# Escorna_CPU_2_40Amt.net
KiCad netlist of a schematic drawn in EAGLE
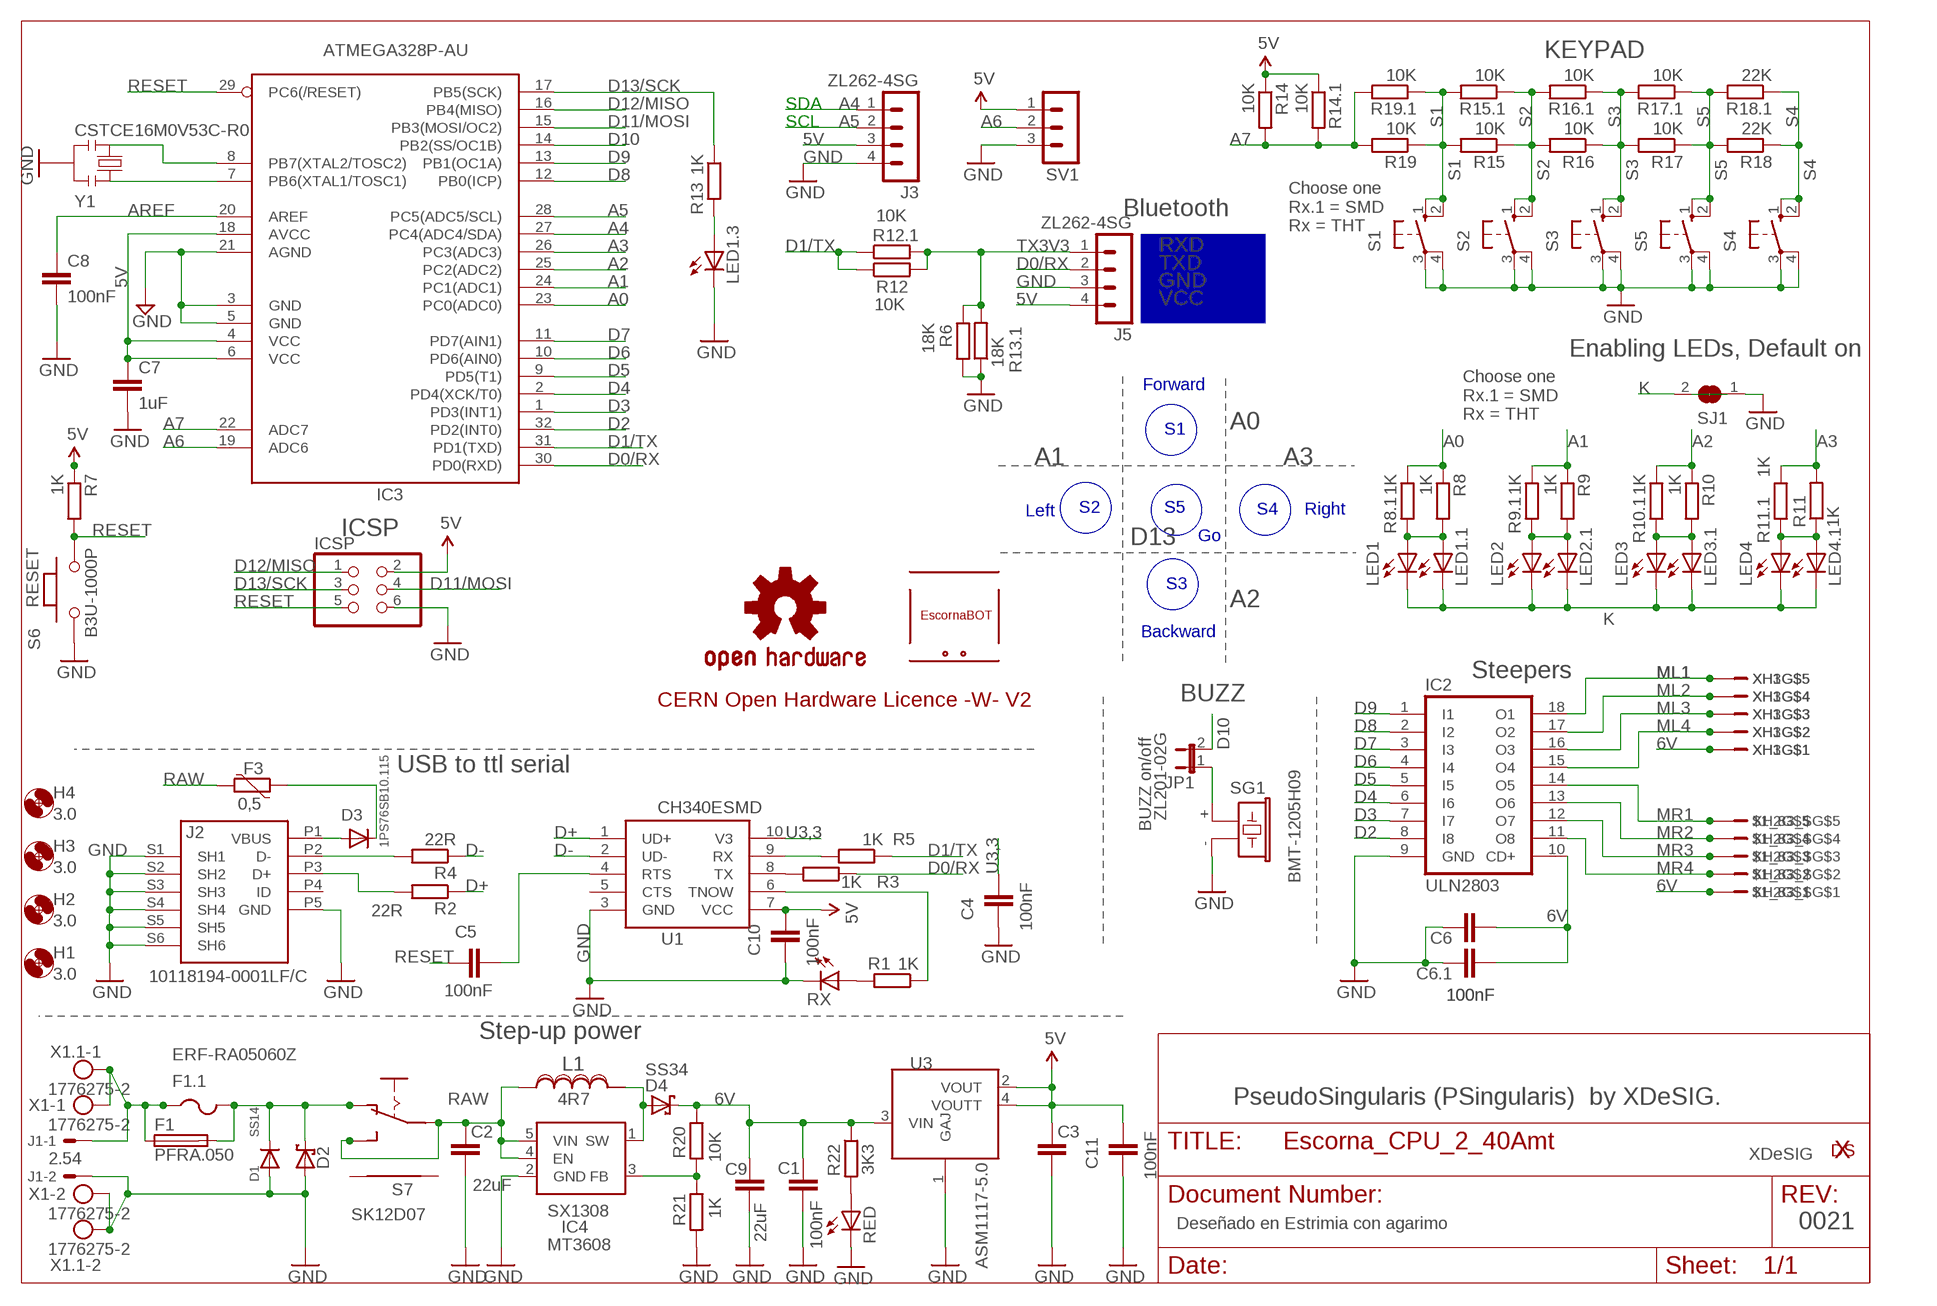
[diagram p0: schematic, sheet 1]

(export (version "E")
  (design (tool "Eeschema 10.0.6"))
  (components
    (comp (ref "$1_82_$")
      (value "XDESIG_XDESIG21")
      (footprint "eagle-import:XDESIG_XDESIG")
      (libsource (lib "eagle-import") (part "XDESIG_XDESIG21"))
    )
    (comp (ref "$1_83_$")
      (value "B5B-XH-A")
      (footprint "eagle-import:B5B-XH-A")
      (libsource (lib "eagle-import") (part "B5B-XH-A"))
    )
    (comp (ref "C1")
      (value "100nF")
      (footprint "eagle-import:C0603-ROUND")
      (fields (field (name "PART_NUMBER") "cl10b104kbnc"))
      (libsource (lib "eagle-import") (part "0015_100NF_0603"))
    )
    (comp (ref "C2")
      (value "22uF")
      (footprint "eagle-import:C1206K")
      (libsource (lib "eagle-import") (part "C-EUC1206K"))
    )
    (comp (ref "C3")
      (value "10uF")
      (footprint "eagle-import:C1206K")
      (libsource (lib "eagle-import") (part "C-EUC1206K"))
    )
    (comp (ref "C4")
      (value "100nF")
      (footprint "eagle-import:C0603-ROUND")
      (fields (field (name "PART_NUMBER") "cl10b104kbnc"))
      (libsource (lib "eagle-import") (part "0015_100NF_0603"))
    )
    (comp (ref "C5")
      (value "100nF")
      (footprint "eagle-import:C0603-ROUND")
      (fields (field (name "PART_NUMBER") "cl10b104kbnc"))
      (libsource (lib "eagle-import") (part "0015_100NF_0603"))
    )
    (comp (ref "C6")
      (value "100nF")
      (footprint "eagle-import:C025-024X044")
      (libsource (lib "eagle-import") (part "C-EU025-024X044"))
    )
    (comp (ref "C6.1")
      (value "100nF")
      (footprint "eagle-import:C0603K")
      (libsource (lib "eagle-import") (part "C-EUC0603K"))
    )
    (comp (ref "C7")
      (value "1uF")
      (footprint "eagle-import:C0603-ROUND")
      (fields (field (name "PART_NUMBER") "1uF_0603/GRM188R61E105KA12D"))
      (libsource (lib "eagle-import") (part "0006_1UF_0603/GRM188R61E105KA12D"))
    )
    (comp (ref "C8")
      (value "100nF")
      (footprint "eagle-import:C0603-ROUND")
      (fields (field (name "PART_NUMBER") "cl10b104kbnc"))
      (libsource (lib "eagle-import") (part "0015_100NF_0603"))
    )
    (comp (ref "C9")
      (value "22uF")
      (footprint "eagle-import:C1206K")
      (libsource (lib "eagle-import") (part "C-EUC1206K"))
    )
    (comp (ref "C10")
      (value "100nF")
      (footprint "eagle-import:C0603-ROUND")
      (fields (field (name "PART_NUMBER") "cl10b104kbnc"))
      (libsource (lib "eagle-import") (part "0015_100NF_0603"))
    )
    (comp (ref "C11")
      (value "100nF")
      (footprint "eagle-import:C0603-ROUND")
      (fields (field (name "PART_NUMBER") "cl10b104kbnc"))
      (libsource (lib "eagle-import") (part "0015_100NF_0603"))
    )
    (comp (ref "D1")
      (value "SS14")
      (footprint "eagle-import:SMADIODE")
      (libsource (lib "eagle-import") (part "DIODESMA"))
    )
    (comp (ref "D2")
      (value "1N5817")
      (footprint "eagle-import:DO41-10")
      (libsource (lib "eagle-import") (part "P4KEXX"))
    )
    (comp (ref "D3")
      (value "1PS76SB10.115")
      (footprint "eagle-import:SOD-323F")
      (libsource (lib "eagle-import") (part "DIODESOD-323F"))
    )
    (comp (ref "D4")
      (value "SS34")
      (footprint "eagle-import:DIODE_SMA")
      (libsource (lib "eagle-import") (part "DIODE_SCHOTTKY-DIODESMA"))
    )
    (comp (ref "ESC")
      (value "ESCORNABOT")
      (footprint "eagle-import:ESCORNA_PEQUE")
      (libsource (lib "eagle-import") (part "ESCORNABOT"))
    )
    (comp (ref "F1")
      (value "PFRA.050")
      (footprint "eagle-import:TE5")
      (libsource (lib "eagle-import") (part "FUSETE5"))
    )
    (comp (ref "F1.1")
      (value "ERF-RA05060Z")
      (footprint "eagle-import:R1206")
      (libsource (lib "eagle-import") (part "PTCFUSE-1206"))
    )
    (comp (ref "F3")
      (value "0,5")
      (footprint "eagle-import:R1206")
      (libsource (lib "eagle-import") (part "PTC1206L"))
    )
    (comp (ref "H1")
      (value "3.0")
      (footprint "eagle-import:3,0")
      (libsource (lib "eagle-import") (part "MOUNT-HOLE3.0"))
    )
    (comp (ref "H2")
      (value "3.0")
      (footprint "eagle-import:3,0")
      (libsource (lib "eagle-import") (part "MOUNT-HOLE3.0"))
    )
    (comp (ref "H3")
      (value "3.0")
      (footprint "eagle-import:3,0")
      (libsource (lib "eagle-import") (part "MOUNT-HOLE3.0"))
    )
    (comp (ref "H4")
      (value "3.0")
      (footprint "eagle-import:3,0")
      (libsource (lib "eagle-import") (part "MOUNT-HOLE3.0"))
    )
    (comp (ref "IC2")
      (value "ULN2803")
      (footprint "eagle-import:DIL18")
      (libsource (lib "eagle-import") (part "ULN2803A"))
    )
    (comp (ref "IC3")
      (value "ATMEGA328P-AU")
      (footprint "eagle-import:TQFP32-08")
      (libsource (lib "eagle-import") (part "0265_ATMEGA328P-AU"))
    )
    (comp (ref "IC4")
      (value "SX1308")
      (footprint "eagle-import:SOT23-6")
      (libsource (lib "eagle-import") (part "SX1308"))
    )
    (comp (ref "ICSP")
      (value "0114_PH254-203DF118A00V")
      (footprint "eagle-import:2X03")
      (fields (field (name "PART_NUMBER") "PH254-203DF118A00V"))
      (libsource (lib "eagle-import") (part "0114_PH254-203DF118A00V"))
    )
    (comp (ref "J1")
      (value "2.54")
      (footprint "eagle-import:6410-02")
      (libsource (lib "eagle-import") (part "22-?-0227-2021"))
    )
    (comp (ref "J2")
      (value "10118194-0001LF/C")
      (footprint "eagle-import:SMARTPRJ_CON2_USB_MICRO_B_AT")
      (libsource (lib "eagle-import") (part "SMARTPRJ_MYCON2_USB-MINI-B"))
    )
    (comp (ref "J3")
      (value "ZL262-4SG")
      (footprint "eagle-import:MA04-1")
      (libsource (lib "eagle-import") (part "MA04-1"))
    )
    (comp (ref "J5")
      (value "ZL262-4SG")
      (footprint "eagle-import:MA04-1")
      (libsource (lib "eagle-import") (part "MA04-1"))
    )
    (comp (ref "JP1")
      (value "ZL201-02G")
      (footprint "eagle-import:JP1")
      (libsource (lib "eagle-import") (part "JP1E"))
    )
    (comp (ref "L1")
      (value "4R7")
      (footprint "eagle-import:SRN6045")
      (fields (field (name "MF") "Bourns") (field (name "MP") "SRN6045-330M"))
      (libsource (lib "eagle-import") (part "SRN6045-330M6045"))
    )
    (comp (ref "LED1")
      (value "LED3MM")
      (footprint "eagle-import:LED3MM")
      (libsource (lib "eagle-import") (part "LED3MM"))
    )
    (comp (ref "LED1.1")
      (value "LEDCHIPLED_0603")
      (footprint "eagle-import:CHIPLED_0603")
      (libsource (lib "eagle-import") (part "LEDCHIPLED_0603"))
    )
    (comp (ref "LED1.3")
      (value "LEDCHIPLED_0603")
      (footprint "eagle-import:CHIPLED_0603")
      (libsource (lib "eagle-import") (part "LEDCHIPLED_0603"))
    )
    (comp (ref "LED2")
      (value "LED3MM")
      (footprint "eagle-import:LED3MM")
      (libsource (lib "eagle-import") (part "LED3MM"))
    )
    (comp (ref "LED2.1")
      (value "LEDCHIPLED_0603")
      (footprint "eagle-import:CHIPLED_0603")
      (libsource (lib "eagle-import") (part "LEDCHIPLED_0603"))
    )
    (comp (ref "LED3")
      (value "LED3MM")
      (footprint "eagle-import:LED3MM")
      (libsource (lib "eagle-import") (part "LED3MM"))
    )
    (comp (ref "LED3.1")
      (value "LEDCHIPLED_0603")
      (footprint "eagle-import:CHIPLED_0603")
      (libsource (lib "eagle-import") (part "LEDCHIPLED_0603"))
    )
    (comp (ref "LED4")
      (value "LED3MM")
      (footprint "eagle-import:LED3MM")
      (libsource (lib "eagle-import") (part "LED3MM"))
    )
    (comp (ref "LED4.1")
      (value "LEDCHIPLED_0603")
      (footprint "eagle-import:CHIPLED_0603")
      (libsource (lib "eagle-import") (part "LEDCHIPLED_0603"))
    )
    (comp (ref "LOGO2")
      (value "OSHW-LOGOL")
      (footprint "eagle-import:ESCORNA_LBRESCORNA_CPU_2_10_SPARKFUN-AESTHETICS_OSHW-LOGO-L")
      (libsource (lib "eagle-import") (part "OSHW-LOGOL"))
    )
    (comp (ref "R1")
      (value "1K")
      (footprint "eagle-import:R0603")
      (libsource (lib "eagle-import") (part "R-EU_R0603"))
    )
    (comp (ref "R2")
      (value "22R")
      (footprint "eagle-import:R0603")
      (libsource (lib "eagle-import") (part "R-EU_R0603"))
    )
    (comp (ref "R3")
      (value "1K")
      (footprint "eagle-import:R0603")
      (libsource (lib "eagle-import") (part "R-EU_R0603"))
    )
    (comp (ref "R4")
      (value "22R")
      (footprint "eagle-import:R0603")
      (libsource (lib "eagle-import") (part "R-EU_R0603"))
    )
    (comp (ref "R5")
      (value "1K")
      (footprint "eagle-import:R0603")
      (libsource (lib "eagle-import") (part "R-EU_R0603"))
    )
    (comp (ref "R6")
      (value "18K")
      (footprint "eagle-import:0204_7")
      (libsource (lib "eagle-import") (part "R-EU_0204/7"))
    )
    (comp (ref "R7")
      (value "1K")
      (footprint "eagle-import:R0603")
      (libsource (lib "eagle-import") (part "R-EU_R0603"))
    )
    (comp (ref "R8")
      (value "1K")
      (footprint "eagle-import:0204_7")
      (libsource (lib "eagle-import") (part "R-EU_0204/7"))
    )
    (comp (ref "R8.1")
      (value "1K")
      (footprint "eagle-import:R0603")
      (libsource (lib "eagle-import") (part "R-EU_R0603"))
    )
    (comp (ref "R9")
      (value "1K")
      (footprint "eagle-import:0204_7")
      (libsource (lib "eagle-import") (part "R-EU_0204/7"))
    )
    (comp (ref "R9.1")
      (value "1K")
      (footprint "eagle-import:R0603")
      (libsource (lib "eagle-import") (part "R-EU_R0603"))
    )
    (comp (ref "R10")
      (value "1K")
      (footprint "eagle-import:0204_7")
      (libsource (lib "eagle-import") (part "R-EU_0204/7"))
    )
    (comp (ref "R10.1")
      (value "1K")
      (footprint "eagle-import:R0603")
      (libsource (lib "eagle-import") (part "R-EU_R0603"))
    )
    (comp (ref "R11")
      (value "1K")
      (footprint "eagle-import:0204_7")
      (libsource (lib "eagle-import") (part "R-EU_0204/7"))
    )
    (comp (ref "R11.1")
      (value "1K")
      (footprint "eagle-import:R0603")
      (libsource (lib "eagle-import") (part "R-EU_R0603"))
    )
    (comp (ref "R12")
      (value "10K")
      (footprint "eagle-import:0204_7")
      (libsource (lib "eagle-import") (part "R-EU_0204/7"))
    )
    (comp (ref "R12.1")
      (value "10K")
      (footprint "eagle-import:R0603")
      (libsource (lib "eagle-import") (part "R-EU_R0603"))
    )
    (comp (ref "R13")
      (value "1K")
      (footprint "eagle-import:R0603")
      (libsource (lib "eagle-import") (part "R-EU_R0603"))
    )
    (comp (ref "R13.1")
      (value "18K")
      (footprint "eagle-import:R0603")
      (libsource (lib "eagle-import") (part "R-EU_R0603"))
    )
    (comp (ref "R14")
      (value "10K")
      (footprint "eagle-import:0204_7")
      (libsource (lib "eagle-import") (part "R-EU_0204/7"))
    )
    (comp (ref "R14.1")
      (value "10K")
      (footprint "eagle-import:R0603")
      (libsource (lib "eagle-import") (part "R-EU_R0603"))
    )
    (comp (ref "R15")
      (value "10K")
      (footprint "eagle-import:0204_7")
      (libsource (lib "eagle-import") (part "R-EU_0204/7"))
    )
    (comp (ref "R15.1")
      (value "10K")
      (footprint "eagle-import:R0603")
      (libsource (lib "eagle-import") (part "R-EU_R0603"))
    )
    (comp (ref "R16")
      (value "10K")
      (footprint "eagle-import:0204_7")
      (libsource (lib "eagle-import") (part "R-EU_0204/7"))
    )
    (comp (ref "R16.1")
      (value "10K")
      (footprint "eagle-import:R0603")
      (libsource (lib "eagle-import") (part "R-EU_R0603"))
    )
    (comp (ref "R17")
      (value "10K")
      (footprint "eagle-import:0204_7")
      (libsource (lib "eagle-import") (part "R-EU_0204/7"))
    )
    (comp (ref "R17.1")
      (value "10K")
      (footprint "eagle-import:R0603")
      (libsource (lib "eagle-import") (part "R-EU_R0603"))
    )
    (comp (ref "R18")
      (value "22K")
      (footprint "eagle-import:0204_7")
      (libsource (lib "eagle-import") (part "R-EU_0204/7"))
    )
    (comp (ref "R18.1")
      (value "22K")
      (footprint "eagle-import:R0603")
      (libsource (lib "eagle-import") (part "R-EU_R0603"))
    )
    (comp (ref "R19")
      (value "10K")
      (footprint "eagle-import:0204_7")
      (libsource (lib "eagle-import") (part "R-EU_0204/7"))
    )
    (comp (ref "R19.1")
      (value "10K")
      (footprint "eagle-import:R0603")
      (libsource (lib "eagle-import") (part "R-EU_R0603"))
    )
    (comp (ref "R20")
      (value "10K")
      (footprint "eagle-import:R0603")
      (libsource (lib "eagle-import") (part "R-EU_R0603"))
    )
    (comp (ref "R21")
      (value "1K")
      (footprint "eagle-import:R0603")
      (libsource (lib "eagle-import") (part "R-EU_R0603"))
    )
    (comp (ref "R22")
      (value "3K3")
      (footprint "eagle-import:R0603")
      (libsource (lib "eagle-import") (part "R-EU_R0603"))
    )
    (comp (ref "RED")
      (value "LEDCHIPLED_0603")
      (footprint "eagle-import:CHIPLED_0603")
      (libsource (lib "eagle-import") (part "LEDCHIPLED_0603"))
    )
    (comp (ref "RX")
      (value "LEDCHIPLED_0603")
      (footprint "eagle-import:CHIPLED_0603")
      (libsource (lib "eagle-import") (part "LEDCHIPLED_0603"))
    )
    (comp (ref "S1")
      (value "40-XX")
      (footprint "eagle-import:B3F-40")
      (fields (field (name "MF") "OMRON COMPONENTS USA") (field (name "MPN") "B3F-4000"))
      (libsource (lib "eagle-import") (part "40-XX"))
    )
    (comp (ref "S2")
      (value "40-XX")
      (footprint "eagle-import:B3F-40")
      (fields (field (name "MF") "OMRON COMPONENTS USA") (field (name "MPN") "B3F-4000"))
      (libsource (lib "eagle-import") (part "40-XX"))
    )
    (comp (ref "S3")
      (value "40-XX")
      (footprint "eagle-import:B3F-40")
      (fields (field (name "MF") "OMRON COMPONENTS USA") (field (name "MPN") "B3F-4000"))
      (libsource (lib "eagle-import") (part "40-XX"))
    )
    (comp (ref "S4")
      (value "40-XX")
      (footprint "eagle-import:B3F-40")
      (fields (field (name "MF") "OMRON COMPONENTS USA") (field (name "MPN") "B3F-4000"))
      (libsource (lib "eagle-import") (part "40-XX"))
    )
    (comp (ref "S5")
      (value "40-XX")
      (footprint "eagle-import:B3F-40")
      (fields (field (name "MF") "OMRON COMPONENTS USA") (field (name "MPN") "B3F-4000"))
      (libsource (lib "eagle-import") (part "40-XX"))
    )
    (comp (ref "S6")
      (value "B3U-1000P")
      (footprint "eagle-import:SMD_157SW")
      (fields (field (name "PART_NUMBER") "IT-1185AP1C-160G-G_T&R"))
      (libsource (lib "eagle-import") (part "0173_IT-1185AP1C-160G-G_T&R"))
    )
    (comp (ref "S7")
      (value "SK12D07")
      (footprint "eagle-import:ESCORNA_SK-12D07")
      (libsource (lib "eagle-import") (part "ESCORNA_SK12F14D"))
    )
    (comp (ref "SG1")
      (value "BMT-1205H09")
      (footprint "eagle-import:F_CM12P")
      (libsource (lib "eagle-import") (part "F/CM12P"))
    )
    (comp (ref "SJ1") (value "SJ") (footprint "eagle-import:SJ") (libsource (lib "eagle-import") (part "SJ")))
    (comp (ref "SV1")
      (value "MA03-1")
      (footprint "eagle-import:MA03-1")
      (libsource (lib "eagle-import") (part "MA03-1"))
    )
    (comp (ref "U1")
      (value "CH340ESMD")
      (footprint "eagle-import:MSOP10")
      (fields (field (name "MF") "WCH") (field (name "MP") "CH340E"))
      (libsource (lib "eagle-import") (part "CH340ESMD"))
    )
    (comp (ref "U3")
      (value "ASM1117-5.0")
      (footprint "eagle-import:SOT223")
      (libsource (lib "eagle-import") (part "ASM1117-3.3"))
    )
    (comp (ref "X1")
      (value "1776275-2")
      (footprint "eagle-import:AK550_2")
      (libsource (lib "eagle-import") (part "AK550/2"))
    )
    (comp (ref "X1.1")
      (value "1776275-2")
      (footprint "eagle-import:AK550_2")
      (fields (field (name "OC_FARNELL") "unknown") (field (name "OC_NEWARK") "unknown"))
      (libsource (lib "eagle-import") (part "AK550/2"))
    )
    (comp (ref "XH1")
      (value "B5B-XH-A")
      (footprint "eagle-import:B5B-XH-A")
      (libsource (lib "eagle-import") (part "B5B-XH-A"))
    )
    (comp (ref "XH2")
      (value "B5B-XH-A")
      (footprint "eagle-import:B5B-XH-A")
      (libsource (lib "eagle-import") (part "B5B-XH-A"))
    )
    (comp (ref "XH3")
      (value "B5B-XH-A")
      (footprint "eagle-import:B5B-XH-A")
      (libsource (lib "eagle-import") (part "B5B-XH-A"))
    )
    (comp (ref "Y1")
      (value "CSTCE16M0V53C-R0")
      (footprint "eagle-import:RESONATOR")
      (fields (field (name "PART_NUMBER") "CSTCE16M0V53-R0"))
      (libsource (lib "eagle-import") (part "0011_CSTCE16M0V53-R0"))
    )
  )
  (nets
    (net (code "1") (name "/6V") (class "Default")
      (node (ref "$1_83_$") (pin "P$1") (pinfunction "1_P$1") (pintype "passive"))
      (node (ref "C1") (pin "2") (pinfunction "2_2") (pintype "passive"))
      (node (ref "C6") (pin "2") (pinfunction "2_2") (pintype "passive"))
      (node (ref "C6.1") (pin "2") (pinfunction "2_2") (pintype "passive"))
      (node (ref "C9") (pin "2") (pinfunction "2_2") (pintype "passive"))
      (node (ref "D4") (pin "C") (pinfunction "C_C") (pintype "passive"))
      (node (ref "IC2") (pin "10") (pinfunction "CD+_10") (pintype "passive"))
      (node (ref "R20") (pin "1") (pinfunction "1_1") (pintype "passive"))
      (node (ref "R22") (pin "1") (pinfunction "1_1") (pintype "passive"))
      (node (ref "U3") (pin "3") (pinfunction "VIN_3") (pintype "bidirectional"))
      (node (ref "XH1") (pin "P$1") (pinfunction "1_P$1") (pintype "passive"))
      (node (ref "XH2") (pin "P$1") (pinfunction "1_P$1") (pintype "passive"))
      (node (ref "XH3") (pin "P$1") (pinfunction "1_P$1") (pintype "passive"))
    )
    (net (code "2") (name "/A0") (class "Default")
      (node (ref "IC3") (pin "23") (pinfunction "PC0(ADC0)_23") (pintype "bidirectional"))
      (node (ref "R8") (pin "1") (pinfunction "1_1") (pintype "passive"))
      (node (ref "R8.1") (pin "1") (pinfunction "1_1") (pintype "passive"))
    )
    (net (code "3") (name "/A1") (class "Default")
      (node (ref "IC3") (pin "24") (pinfunction "PC1(ADC1)_24") (pintype "bidirectional"))
      (node (ref "R9") (pin "1") (pinfunction "1_1") (pintype "passive"))
      (node (ref "R9.1") (pin "1") (pinfunction "1_1") (pintype "passive"))
    )
    (net (code "4") (name "/A2") (class "Default")
      (node (ref "IC3") (pin "25") (pinfunction "PC2(ADC2)_25") (pintype "bidirectional"))
      (node (ref "R10") (pin "1") (pinfunction "1_1") (pintype "passive"))
      (node (ref "R10.1") (pin "1") (pinfunction "1_1") (pintype "passive"))
    )
    (net (code "5") (name "/A3") (class "Default")
      (node (ref "IC3") (pin "26") (pinfunction "PC3(ADC3)_26") (pintype "bidirectional"))
      (node (ref "R11") (pin "2") (pinfunction "2_2") (pintype "passive"))
      (node (ref "R11.1") (pin "1") (pinfunction "1_1") (pintype "passive"))
    )
    (net (code "6") (name "/A4") (class "Default")
      (node (ref "IC3") (pin "27") (pinfunction "PC4(ADC4/SDA)_27") (pintype "bidirectional"))
      (node (ref "J3") (pin "1") (pinfunction "1_1") (pintype "passive"))
    )
    (net (code "7") (name "/A5") (class "Default")
      (node (ref "IC3") (pin "28") (pinfunction "PC5(ADC5/SCL)_28") (pintype "bidirectional"))
      (node (ref "J3") (pin "2") (pinfunction "2_2") (pintype "passive"))
    )
    (net (code "8") (name "/A6") (class "Default")
      (node (ref "IC3") (pin "19") (pinfunction "ADC6_19") (pintype "bidirectional"))
      (node (ref "SV1") (pin "2") (pinfunction "2_2") (pintype "passive"))
    )
    (net (code "9") (name "/A7") (class "Default")
      (node (ref "IC3") (pin "22") (pinfunction "ADC7_22") (pintype "bidirectional"))
      (node (ref "R14") (pin "2") (pinfunction "2_2") (pintype "passive"))
      (node (ref "R14.1") (pin "2") (pinfunction "2_2") (pintype "passive"))
      (node (ref "R19") (pin "2") (pinfunction "2_2") (pintype "passive"))
      (node (ref "R19.1") (pin "2") (pinfunction "2_2") (pintype "passive"))
    )
    (net (code "10") (name "/AREF") (class "Default")
      (node (ref "C8") (pin "1") (pinfunction "1_1") (pintype "passive"))
      (node (ref "IC3") (pin "20") (pinfunction "AREF_20") (pintype "bidirectional"))
    )
    (net (code "11") (name "/D+") (class "Default")
      (node (ref "R2") (pin "1") (pinfunction "1_1") (pintype "passive"))
      (node (ref "U1") (pin "1") (pinfunction "UD+_1") (pintype "bidirectional"))
    )
    (net (code "12") (name "/D-") (class "Default")
      (node (ref "R4") (pin "1") (pinfunction "1_1") (pintype "passive"))
      (node (ref "U1") (pin "2") (pinfunction "UD-_2") (pintype "bidirectional"))
    )
    (net (code "13") (name "/D0{slash}RX") (class "Default")
      (node (ref "IC3") (pin "30") (pinfunction "PD0(RXD)_30") (pintype "bidirectional"))
      (node (ref "J5") (pin "2") (pinfunction "2_2") (pintype "passive"))
      (node (ref "R3") (pin "1") (pinfunction "1_1") (pintype "passive"))
    )
    (net (code "14") (name "/D1{slash}TX") (class "Default")
      (node (ref "IC3") (pin "31") (pinfunction "PD1(TXD)_31") (pintype "bidirectional"))
      (node (ref "R12") (pin "1") (pinfunction "1_1") (pintype "passive"))
      (node (ref "R12.1") (pin "1") (pinfunction "1_1") (pintype "passive"))
      (node (ref "R5") (pin "1") (pinfunction "1_1") (pintype "passive"))
    )
    (net (code "15") (name "/D2") (class "Default")
      (node (ref "IC2") (pin "8") (pinfunction "I8_8") (pintype "input"))
      (node (ref "IC3") (pin "32") (pinfunction "PD2(INT0)_32") (pintype "bidirectional"))
    )
    (net (code "16") (name "/D3") (class "Default")
      (node (ref "IC2") (pin "7") (pinfunction "I7_7") (pintype "input"))
      (node (ref "IC3") (pin "1") (pinfunction "PD3(INT1)_1") (pintype "bidirectional"))
    )
    (net (code "17") (name "/D4") (class "Default")
      (node (ref "IC2") (pin "6") (pinfunction "I6_6") (pintype "input"))
      (node (ref "IC3") (pin "2") (pinfunction "PD4(XCK/T0)_2") (pintype "bidirectional"))
    )
    (net (code "18") (name "/D5") (class "Default")
      (node (ref "IC2") (pin "5") (pinfunction "I5_5") (pintype "input"))
      (node (ref "IC3") (pin "9") (pinfunction "PD5(T1)_9") (pintype "bidirectional"))
    )
    (net (code "19") (name "/D6") (class "Default")
      (node (ref "IC2") (pin "4") (pinfunction "I4_4") (pintype "input"))
      (node (ref "IC3") (pin "10") (pinfunction "PD6(AIN0)_10") (pintype "bidirectional"))
    )
    (net (code "20") (name "/D7") (class "Default")
      (node (ref "IC2") (pin "3") (pinfunction "I3_3") (pintype "input"))
      (node (ref "IC3") (pin "11") (pinfunction "PD7(AIN1)_11") (pintype "bidirectional"))
    )
    (net (code "21") (name "/D8") (class "Default")
      (node (ref "IC2") (pin "2") (pinfunction "I2_2") (pintype "input"))
      (node (ref "IC3") (pin "12") (pinfunction "PB0(ICP)_12") (pintype "bidirectional"))
    )
    (net (code "22") (name "/D9") (class "Default")
      (node (ref "IC2") (pin "1") (pinfunction "I1_1") (pintype "input"))
      (node (ref "IC3") (pin "13") (pinfunction "PB1(OC1A)_13") (pintype "bidirectional"))
    )
    (net (code "23") (name "/D10") (class "Default")
      (node (ref "IC3") (pin "14") (pinfunction "PB2(SS/OC1B)_14") (pintype "bidirectional"))
      (node (ref "JP1") (pin "2") (pinfunction "2_2") (pintype "passive"))
    )
    (net (code "24") (name "/D11{slash}MOSI") (class "Default")
      (node (ref "IC3") (pin "15") (pinfunction "PB3(MOSI/OC2)_15") (pintype "bidirectional"))
      (node (ref "ICSP") (pin "4") (pinfunction "4_4") (pintype "passive"))
    )
    (net (code "25") (name "/D12{slash}MISO") (class "Default")
      (node (ref "IC3") (pin "16") (pinfunction "PB4(MISO)_16") (pintype "bidirectional"))
      (node (ref "ICSP") (pin "1") (pinfunction "1_1") (pintype "passive"))
    )
    (net (code "26") (name "/D13{slash}SCK") (class "Default")
      (node (ref "IC3") (pin "17") (pinfunction "PB5(SCK)_17") (pintype "bidirectional"))
      (node (ref "ICSP") (pin "3") (pinfunction "3_3") (pintype "passive"))
      (node (ref "R13") (pin "1") (pinfunction "1_1") (pintype "passive"))
    )
    (net (code "27") (name "/K") (class "Default")
      (node (ref "LED1") (pin "K") (pinfunction "C_K") (pintype "passive"))
      (node (ref "LED1.1") (pin "C") (pinfunction "C_C") (pintype "passive"))
      (node (ref "LED2") (pin "K") (pinfunction "C_K") (pintype "passive"))
      (node (ref "LED2.1") (pin "C") (pinfunction "C_C") (pintype "passive"))
      (node (ref "LED3") (pin "K") (pinfunction "C_K") (pintype "passive"))
      (node (ref "LED3.1") (pin "C") (pinfunction "C_C") (pintype "passive"))
      (node (ref "LED4") (pin "K") (pinfunction "C_K") (pintype "passive"))
      (node (ref "LED4.1") (pin "C") (pinfunction "C_C") (pintype "passive"))
      (node (ref "SJ1") (pin "2") (pinfunction "2_2") (pintype "passive"))
    )
    (net (code "28") (name "/ML1") (class "Default")
      (node (ref "IC2") (pin "18") (pinfunction "O1_18") (pintype "open_collector"))
      (node (ref "XH1") (pin "P$5") (pinfunction "1_P$5") (pintype "passive"))
      (node (ref "XH3") (pin "P$5") (pinfunction "1_P$5") (pintype "passive"))
    )
    (net (code "29") (name "/ML2") (class "Default")
      (node (ref "IC2") (pin "17") (pinfunction "O2_17") (pintype "open_collector"))
      (node (ref "XH1") (pin "P$4") (pinfunction "1_P$4") (pintype "passive"))
      (node (ref "XH3") (pin "P$4") (pinfunction "1_P$4") (pintype "passive"))
    )
    (net (code "30") (name "/ML3") (class "Default")
      (node (ref "IC2") (pin "16") (pinfunction "O3_16") (pintype "open_collector"))
      (node (ref "XH1") (pin "P$3") (pinfunction "1_P$3") (pintype "passive"))
      (node (ref "XH3") (pin "P$3") (pinfunction "1_P$3") (pintype "passive"))
    )
    (net (code "31") (name "/ML4") (class "Default")
      (node (ref "IC2") (pin "15") (pinfunction "O4_15") (pintype "open_collector"))
      (node (ref "XH1") (pin "P$2") (pinfunction "1_P$2") (pintype "passive"))
      (node (ref "XH3") (pin "P$2") (pinfunction "1_P$2") (pintype "passive"))
    )
    (net (code "32") (name "/MR1") (class "Default")
      (node (ref "$1_83_$") (pin "P$5") (pinfunction "1_P$5") (pintype "passive"))
      (node (ref "IC2") (pin "14") (pinfunction "O5_14") (pintype "open_collector"))
      (node (ref "XH2") (pin "P$5") (pinfunction "1_P$5") (pintype "passive"))
    )
    (net (code "33") (name "/MR2") (class "Default")
      (node (ref "$1_83_$") (pin "P$4") (pinfunction "1_P$4") (pintype "passive"))
      (node (ref "IC2") (pin "13") (pinfunction "O6_13") (pintype "open_collector"))
      (node (ref "XH2") (pin "P$4") (pinfunction "1_P$4") (pintype "passive"))
    )
    (net (code "34") (name "/MR3") (class "Default")
      (node (ref "$1_83_$") (pin "P$3") (pinfunction "1_P$3") (pintype "passive"))
      (node (ref "IC2") (pin "12") (pinfunction "O7_12") (pintype "open_collector"))
      (node (ref "XH2") (pin "P$3") (pinfunction "1_P$3") (pintype "passive"))
    )
    (net (code "35") (name "/MR4") (class "Default")
      (node (ref "$1_83_$") (pin "P$2") (pinfunction "1_P$2") (pintype "passive"))
      (node (ref "IC2") (pin "11") (pinfunction "O8_11") (pintype "open_collector"))
      (node (ref "XH2") (pin "P$2") (pinfunction "1_P$2") (pintype "passive"))
    )
    (net (code "36") (name "/RAW") (class "Default")
      (node (ref "C2") (pin "2") (pinfunction "2_2") (pintype "passive"))
      (node (ref "F3") (pin "2") (pinfunction "2_2") (pintype "passive"))
      (node (ref "IC4") (pin "4") (pinfunction "EN_4") (pintype "bidirectional"))
      (node (ref "IC4") (pin "5") (pinfunction "VIN_5") (pintype "bidirectional"))
      (node (ref "L1") (pin "2") (pinfunction "2_2") (pintype "passive"))
      (node (ref "S7") (pin "P$1") (pinfunction "P_P$1") (pintype "passive"))
      (node (ref "S7") (pin "P$3") (pinfunction "S_P$3") (pintype "passive"))
    )
    (net (code "37") (name "/RESET") (class "Default")
      (node (ref "C5") (pin "1") (pinfunction "1_1") (pintype "passive"))
      (node (ref "IC3") (pin "29") (pinfunction "PC6(/RESET)_29") (pintype "bidirectional"))
      (node (ref "ICSP") (pin "5") (pinfunction "5_5") (pintype "passive"))
      (node (ref "R7") (pin "2") (pinfunction "2_2") (pintype "passive"))
      (node (ref "S6") (pin "2") (pinfunction "2_2") (pintype "passive"))
    )
    (net (code "38") (name "/S1") (class "Default")
      (node (ref "R15") (pin "2") (pinfunction "2_2") (pintype "passive"))
      (node (ref "R15.1") (pin "2") (pinfunction "2_2") (pintype "passive"))
      (node (ref "R19") (pin "1") (pinfunction "1_1") (pintype "passive"))
      (node (ref "R19.1") (pin "1") (pinfunction "1_1") (pintype "passive"))
      (node (ref "S1") (pin "1") (pinfunction "S_1") (pintype "passive"))
      (node (ref "S1") (pin "2") (pinfunction "S1_2") (pintype "passive"))
    )
    (net (code "39") (name "/S2") (class "Default")
      (node (ref "R15") (pin "1") (pinfunction "1_1") (pintype "passive"))
      (node (ref "R15.1") (pin "1") (pinfunction "1_1") (pintype "passive"))
      (node (ref "R16") (pin "2") (pinfunction "2_2") (pintype "passive"))
      (node (ref "R16.1") (pin "2") (pinfunction "2_2") (pintype "passive"))
      (node (ref "S2") (pin "1") (pinfunction "S_1") (pintype "passive"))
      (node (ref "S2") (pin "2") (pinfunction "S1_2") (pintype "passive"))
    )
    (net (code "40") (name "/S3") (class "Default")
      (node (ref "R16") (pin "1") (pinfunction "1_1") (pintype "passive"))
      (node (ref "R16.1") (pin "1") (pinfunction "1_1") (pintype "passive"))
      (node (ref "R17") (pin "2") (pinfunction "2_2") (pintype "passive"))
      (node (ref "R17.1") (pin "2") (pinfunction "2_2") (pintype "passive"))
      (node (ref "S3") (pin "1") (pinfunction "S_1") (pintype "passive"))
      (node (ref "S3") (pin "2") (pinfunction "S1_2") (pintype "passive"))
    )
    (net (code "41") (name "/S4") (class "Default")
      (node (ref "R18") (pin "1") (pinfunction "1_1") (pintype "passive"))
      (node (ref "R18.1") (pin "1") (pinfunction "1_1") (pintype "passive"))
      (node (ref "S4") (pin "1") (pinfunction "S_1") (pintype "passive"))
      (node (ref "S4") (pin "2") (pinfunction "S1_2") (pintype "passive"))
    )
    (net (code "42") (name "/S5") (class "Default")
      (node (ref "R17") (pin "1") (pinfunction "1_1") (pintype "passive"))
      (node (ref "R17.1") (pin "1") (pinfunction "1_1") (pintype "passive"))
      (node (ref "R18") (pin "2") (pinfunction "2_2") (pintype "passive"))
      (node (ref "R18.1") (pin "2") (pinfunction "2_2") (pintype "passive"))
      (node (ref "S5") (pin "1") (pinfunction "S_1") (pintype "passive"))
      (node (ref "S5") (pin "2") (pinfunction "S1_2") (pintype "passive"))
    )
    (net (code "43") (name "/TX3V3") (class "Default")
      (node (ref "J5") (pin "1") (pinfunction "1_1") (pintype "passive"))
      (node (ref "R12") (pin "2") (pinfunction "2_2") (pintype "passive"))
      (node (ref "R12.1") (pin "2") (pinfunction "2_2") (pintype "passive"))
      (node (ref "R13.1") (pin "2") (pinfunction "2_2") (pintype "passive"))
      (node (ref "R6") (pin "1") (pinfunction "1_1") (pintype "passive"))
    )
    (net (code "44") (name "/U3,3") (class "Default")
      (node (ref "C4") (pin "2") (pinfunction "2_2") (pintype "passive"))
      (node (ref "U1") (pin "10") (pinfunction "V3_10") (pintype "power_in"))
    )
    (net (code "45") (name "5V") (class "Default")
      (node (ref "C10") (pin "2") (pinfunction "2_2") (pintype "passive"))
      (node (ref "C11") (pin "2") (pinfunction "2_2") (pintype "passive"))
      (node (ref "C3") (pin "2") (pinfunction "2_2") (pintype "passive"))
      (node (ref "C7") (pin "1") (pinfunction "1_1") (pintype "passive"))
      (node (ref "IC3") (pin "18") (pinfunction "AVCC_18") (pintype "bidirectional"))
      (node (ref "IC3") (pin "4") (pinfunction "VCC_4") (pintype "bidirectional"))
      (node (ref "IC3") (pin "6") (pinfunction "VCC_6") (pintype "bidirectional"))
      (node (ref "ICSP") (pin "2") (pinfunction "2_2") (pintype "passive"))
      (node (ref "J3") (pin "3") (pinfunction "3_3") (pintype "passive"))
      (node (ref "J5") (pin "4") (pinfunction "4_4") (pintype "passive"))
      (node (ref "R14") (pin "1") (pinfunction "1_1") (pintype "passive"))
      (node (ref "R14.1") (pin "1") (pinfunction "1_1") (pintype "passive"))
      (node (ref "R7") (pin "1") (pinfunction "1_1") (pintype "passive"))
      (node (ref "SV1") (pin "1") (pinfunction "1_1") (pintype "passive"))
      (node (ref "U1") (pin "7") (pinfunction "VCC_7") (pintype "power_in"))
      (node (ref "U3") (pin "2") (pinfunction "VOUT_2") (pintype "bidirectional"))
      (node (ref "U3") (pin "4") (pinfunction "VOUTT_4") (pintype "bidirectional"))
    )
    (net (code "46") (name "GND") (class "Default")
      (node (ref "C1") (pin "1") (pinfunction "1_1") (pintype "passive"))
      (node (ref "C10") (pin "1") (pinfunction "1_1") (pintype "passive"))
      (node (ref "C11") (pin "1") (pinfunction "1_1") (pintype "passive"))
      (node (ref "C2") (pin "1") (pinfunction "1_1") (pintype "passive"))
      (node (ref "C3") (pin "1") (pinfunction "1_1") (pintype "passive"))
      (node (ref "C4") (pin "1") (pinfunction "1_1") (pintype "passive"))
      (node (ref "C6") (pin "1") (pinfunction "1_1") (pintype "passive"))
      (node (ref "C6.1") (pin "1") (pinfunction "1_1") (pintype "passive"))
      (node (ref "C7") (pin "2") (pinfunction "2_2") (pintype "passive"))
      (node (ref "C8") (pin "2") (pinfunction "2_2") (pintype "passive"))
      (node (ref "C9") (pin "1") (pinfunction "1_1") (pintype "passive"))
      (node (ref "D1") (pin "A") (pinfunction "A_A") (pintype "passive"))
      (node (ref "D2") (pin "A") (pinfunction "A_A") (pintype "passive"))
      (node (ref "IC2") (pin "9") (pinfunction "GND_9") (pintype "power_in"))
      (node (ref "IC3") (pin "21") (pinfunction "AGND_21") (pintype "bidirectional"))
      (node (ref "IC3") (pin "3") (pinfunction "GND_3") (pintype "bidirectional"))
      (node (ref "IC3") (pin "5") (pinfunction "GND_5") (pintype "bidirectional"))
      (node (ref "IC4") (pin "2") (pinfunction "GND_2") (pintype "bidirectional"))
      (node (ref "ICSP") (pin "6") (pinfunction "6_6") (pintype "passive"))
      (node (ref "J1") (pin "2") (pinfunction "S_2") (pintype "passive"))
      (node (ref "J2") (pin "P5") (pinfunction "GND_P5") (pintype "passive"))
      (node (ref "J2") (pin "S1") (pinfunction "SH1_S1") (pintype "passive"))
      (node (ref "J2") (pin "S2") (pinfunction "SH2_S2") (pintype "passive"))
      (node (ref "J2") (pin "S3") (pinfunction "SH3_S3") (pintype "passive"))
      (node (ref "J2") (pin "S4") (pinfunction "SH4_S4") (pintype "passive"))
      (node (ref "J2") (pin "S5") (pinfunction "SH5_S5") (pintype "passive"))
      (node (ref "J2") (pin "S6") (pinfunction "SH6_S6") (pintype "passive"))
      (node (ref "J3") (pin "4") (pinfunction "4_4") (pintype "passive"))
      (node (ref "J5") (pin "3") (pinfunction "3_3") (pintype "passive"))
      (node (ref "LED1.3") (pin "C") (pinfunction "C_C") (pintype "passive"))
      (node (ref "R13.1") (pin "1") (pinfunction "1_1") (pintype "passive"))
      (node (ref "R21") (pin "2") (pinfunction "2_2") (pintype "passive"))
      (node (ref "R6") (pin "2") (pinfunction "2_2") (pintype "passive"))
      (node (ref "RED") (pin "C") (pinfunction "C_C") (pintype "passive"))
      (node (ref "RX") (pin "C") (pinfunction "C_C") (pintype "passive"))
      (node (ref "S1") (pin "3") (pinfunction "P_3") (pintype "passive"))
      (node (ref "S1") (pin "4") (pinfunction "P1_4") (pintype "passive"))
      (node (ref "S2") (pin "3") (pinfunction "P_3") (pintype "passive"))
      (node (ref "S2") (pin "4") (pinfunction "P1_4") (pintype "passive"))
      (node (ref "S3") (pin "3") (pinfunction "P_3") (pintype "passive"))
      (node (ref "S3") (pin "4") (pinfunction "P1_4") (pintype "passive"))
      (node (ref "S4") (pin "3") (pinfunction "P_3") (pintype "passive"))
      (node (ref "S4") (pin "4") (pinfunction "P1_4") (pintype "passive"))
      (node (ref "S5") (pin "3") (pinfunction "P_3") (pintype "passive"))
      (node (ref "S5") (pin "4") (pinfunction "P1_4") (pintype "passive"))
      (node (ref "S6") (pin "1") (pinfunction "1_1") (pintype "passive"))
      (node (ref "SG1") (pin "-") (pinfunction "2_-") (pintype "passive"))
      (node (ref "SJ1") (pin "1") (pinfunction "1_1") (pintype "passive"))
      (node (ref "SV1") (pin "3") (pinfunction "3_3") (pintype "passive"))
      (node (ref "U1") (pin "3") (pinfunction "GND_3") (pintype "power_in"))
      (node (ref "U3") (pin "1") (pinfunction "GAJ_1") (pintype "bidirectional"))
      (node (ref "X1") (pin "2") (pinfunction "KL_2") (pintype "passive"))
      (node (ref "X1.1") (pin "2") (pinfunction "KL_2") (pintype "passive"))
      (node (ref "Y1") (pin "2") (pinfunction "2_2") (pintype "passive"))
    )
    (net (code "47") (name "Net-(D3-PadC)") (class "Default")
      (node (ref "D3") (pin "C") (pinfunction "C_C") (pintype "passive"))
      (node (ref "F3") (pin "1") (pinfunction "1_1") (pintype "passive"))
    )
    (net (code "48") (name "Net-(IC3-PB6(XTAL1{slash}TOSC1))") (class "Default")
      (node (ref "IC3") (pin "7") (pinfunction "PB6(XTAL1/TOSC1)_7") (pintype "bidirectional"))
      (node (ref "Y1") (pin "1") (pinfunction "1_1") (pintype "passive"))
    )
    (net (code "49") (name "Net-(IC3-PB7(XTAL2{slash}TOSC2))") (class "Default")
      (node (ref "IC3") (pin "8") (pinfunction "PB7(XTAL2/TOSC2)_8") (pintype "bidirectional"))
      (node (ref "Y1") (pin "3") (pinfunction "3_3") (pintype "passive"))
    )
    (net (code "50") (name "Net-(IC4-FB)") (class "Default")
      (node (ref "IC4") (pin "3") (pinfunction "FB_3") (pintype "bidirectional"))
      (node (ref "R20") (pin "2") (pinfunction "2_2") (pintype "passive"))
      (node (ref "R21") (pin "1") (pinfunction "1_1") (pintype "passive"))
    )
    (net (code "51") (name "Net-(IC4-SW)") (class "Default")
      (node (ref "D4") (pin "A") (pinfunction "A_A") (pintype "passive"))
      (node (ref "IC4") (pin "1") (pinfunction "SW_1") (pintype "bidirectional"))
      (node (ref "L1") (pin "1") (pinfunction "1_1") (pintype "passive"))
    )
    (net (code "52") (name "Net-(J1A-S)") (class "Default")
      (node (ref "F1") (pin "1") (pinfunction "1_1") (pintype "passive"))
      (node (ref "F1.1") (pin "1") (pinfunction "1_1") (pintype "passive"))
      (node (ref "J1") (pin "1") (pinfunction "S_1") (pintype "passive"))
      (node (ref "X1") (pin "1") (pinfunction "KL_1") (pintype "passive"))
      (node (ref "X1.1") (pin "1") (pinfunction "KL_1") (pintype "passive"))
    )
    (net (code "53") (name "Net-(J2-D+)") (class "Default")
      (node (ref "J2") (pin "P3") (pinfunction "D+_P3") (pintype "bidirectional"))
      (node (ref "R2") (pin "2") (pinfunction "2_2") (pintype "passive"))
    )
    (net (code "54") (name "Net-(J2-D-)") (class "Default")
      (node (ref "J2") (pin "P2") (pinfunction "D-_P2") (pintype "bidirectional"))
      (node (ref "R4") (pin "2") (pinfunction "2_2") (pintype "passive"))
    )
    (net (code "55") (name "Net-(J2-VBUS)") (class "Default")
      (node (ref "D3") (pin "A") (pinfunction "A_A") (pintype "passive"))
      (node (ref "J2") (pin "P1") (pinfunction "VBUS_P1") (pintype "power_in"))
    )
    (net (code "56") (name "Net-(LED1-PadA)") (class "Default")
      (node (ref "LED1") (pin "A") (pinfunction "A_A") (pintype "passive"))
      (node (ref "LED1.1") (pin "A") (pinfunction "A_A") (pintype "passive"))
      (node (ref "R8") (pin "2") (pinfunction "2_2") (pintype "passive"))
      (node (ref "R8.1") (pin "2") (pinfunction "2_2") (pintype "passive"))
    )
    (net (code "57") (name "Net-(LED1.3-PadA)") (class "Default")
      (node (ref "LED1.3") (pin "A") (pinfunction "A_A") (pintype "passive"))
      (node (ref "R13") (pin "2") (pinfunction "2_2") (pintype "passive"))
    )
    (net (code "58") (name "Net-(LED2-PadA)") (class "Default")
      (node (ref "LED2") (pin "A") (pinfunction "A_A") (pintype "passive"))
      (node (ref "LED2.1") (pin "A") (pinfunction "A_A") (pintype "passive"))
      (node (ref "R9") (pin "2") (pinfunction "2_2") (pintype "passive"))
      (node (ref "R9.1") (pin "2") (pinfunction "2_2") (pintype "passive"))
    )
    (net (code "59") (name "Net-(LED3-PadA)") (class "Default")
      (node (ref "LED3") (pin "A") (pinfunction "A_A") (pintype "passive"))
      (node (ref "LED3.1") (pin "A") (pinfunction "A_A") (pintype "passive"))
      (node (ref "R10") (pin "2") (pinfunction "2_2") (pintype "passive"))
      (node (ref "R10.1") (pin "2") (pinfunction "2_2") (pintype "passive"))
    )
    (net (code "60") (name "Net-(LED4-PadA)") (class "Default")
      (node (ref "LED4") (pin "A") (pinfunction "A_A") (pintype "passive"))
      (node (ref "LED4.1") (pin "A") (pinfunction "A_A") (pintype "passive"))
      (node (ref "R11") (pin "1") (pinfunction "1_1") (pintype "passive"))
      (node (ref "R11.1") (pin "2") (pinfunction "2_2") (pintype "passive"))
    )
    (net (code "61") (name "Net-(R1-Pad2)") (class "Default")
      (node (ref "R1") (pin "2") (pinfunction "2_2") (pintype "passive"))
      (node (ref "RX") (pin "A") (pinfunction "A_A") (pintype "passive"))
    )
    (net (code "62") (name "Net-(R22-Pad2)") (class "Default")
      (node (ref "R22") (pin "2") (pinfunction "2_2") (pintype "passive"))
      (node (ref "RED") (pin "A") (pinfunction "A_A") (pintype "passive"))
    )
    (net (code "63") (name "Net-(S7-O)") (class "Default")
      (node (ref "D1") (pin "C") (pinfunction "C_C") (pintype "passive"))
      (node (ref "D2") (pin "C") (pinfunction "C_C") (pintype "passive"))
      (node (ref "F1") (pin "2") (pinfunction "2_2") (pintype "passive"))
      (node (ref "F1.1") (pin "2") (pinfunction "2_2") (pintype "passive"))
      (node (ref "S7") (pin "P$2") (pinfunction "O_P$2") (pintype "passive"))
    )
    (net (code "64") (name "Net-(SG1-1)") (class "Default")
      (node (ref "JP1") (pin "1") (pinfunction "1_1") (pintype "passive"))
      (node (ref "SG1") (pin "+") (pinfunction "1_+") (pintype "passive"))
    )
    (net (code "65") (name "Net-(U1-RTS)") (class "Default")
      (node (ref "C5") (pin "2") (pinfunction "2_2") (pintype "passive"))
      (node (ref "U1") (pin "4") (pinfunction "RTS_4") (pintype "output"))
    )
    (net (code "66") (name "Net-(U1-RX)") (class "Default")
      (node (ref "R5") (pin "2") (pinfunction "2_2") (pintype "passive"))
      (node (ref "U1") (pin "9") (pinfunction "RX_9") (pintype "input"))
    )
    (net (code "67") (name "Net-(U1-TNOW)") (class "Default")
      (node (ref "R1") (pin "1") (pinfunction "1_1") (pintype "passive"))
      (node (ref "U1") (pin "6") (pinfunction "TNOW_6") (pintype "output"))
    )
    (net (code "68") (name "Net-(U1-TX)") (class "Default")
      (node (ref "R3") (pin "2") (pinfunction "2_2") (pintype "passive"))
      (node (ref "U1") (pin "8") (pinfunction "TX_8") (pintype "output"))
    )
    (net (code "69") (name "unconnected-(J2-ID-PadP4)") (class "Default")
      (node (ref "J2") (pin "P4") (pinfunction "ID_P4") (pintype "bidirectional"))
    )
    (net (code "70") (name "unconnected-(S7-P$1-PadP$4)") (class "Default")
      (node (ref "S7") (pin "P$4") (pinfunction "P$1_P$4") (pintype "passive"))
    )
    (net (code "71") (name "unconnected-(S7-P$2-PadP$5)") (class "Default")
      (node (ref "S7") (pin "P$5") (pinfunction "P$2_P$5") (pintype "bidirectional"))
    )
    (net (code "72") (name "unconnected-(U1-CTS-Pad5)") (class "Default")
      (node (ref "U1") (pin "5") (pinfunction "CTS_5") (pintype "input"))
    )
  )
)
